# ArduinoUnoShield.net
KiCad netlist of a schematic drawn in Altium Designer
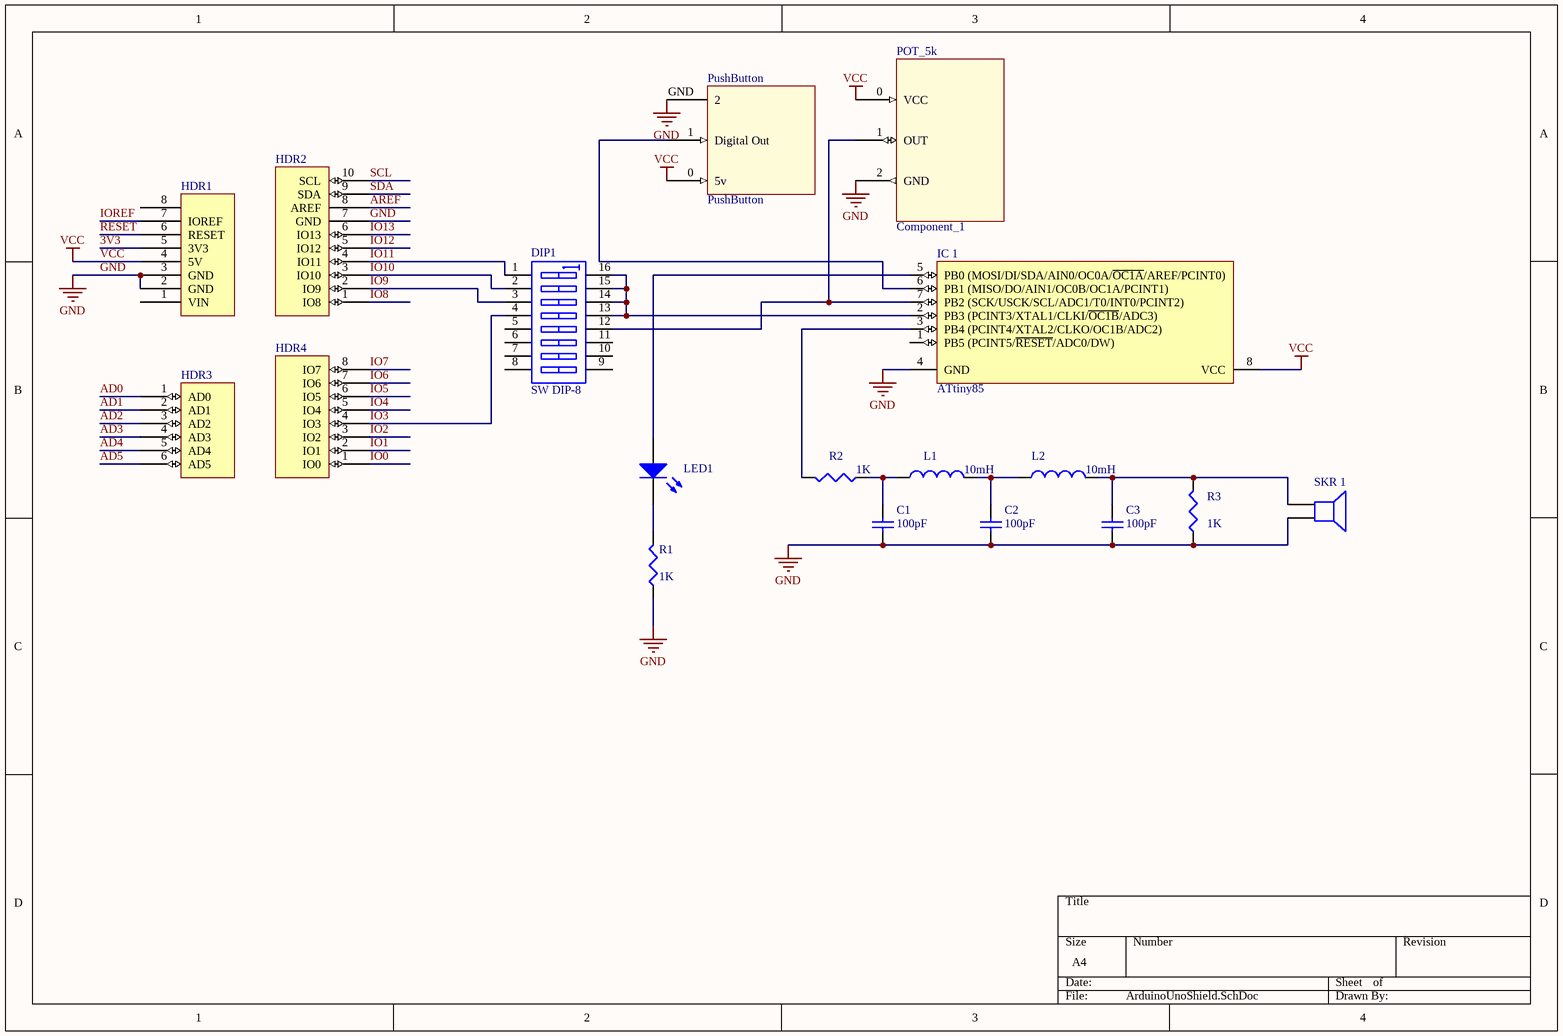
[diagram p0: ArduinoUnoShield.SchDoc]

(export (version "E")
  (design (tool "Eeschema 10.0.6"))
  (components
    (comp (ref "C1")
      (value "100pF")
      (footprint "1608[0603]")
      (description "Capacitor (Semiconductor SIM Model)")
      (fields (field (name "Comment") "Cap Semi") (field (name "PUBLISHER") "Altium Limited"))
      (libsource (lib "Miscellaneous Devices") (part "Cap Semi"))
    )
    (comp (ref "C2")
      (value "100pF")
      (footprint "1608[0603]")
      (description "Capacitor (Semiconductor SIM Model)")
      (fields (field (name "Comment") "Cap Semi") (field (name "PUBLISHER") "Altium Limited"))
      (libsource (lib "Miscellaneous Devices") (part "Cap Semi"))
    )
    (comp (ref "C3")
      (value "100pF")
      (footprint "1608[0603]")
      (description "Capacitor (Semiconductor SIM Model)")
      (fields (field (name "Comment") "Cap Semi") (field (name "PUBLISHER") "Altium Limited"))
      (libsource (lib "Miscellaneous Devices") (part "Cap Semi"))
    )
    (comp (ref "DIP1")
      (value "SW DIP-8")
      (footprint "DIP_SW_8WAY_SMD")
      (description "DIP Switch, 8 Position, SPST")
      (fields (field (name "PUBLISHER") "Altium Limited"))
      (libsource (lib "Miscellaneous Devices") (part "SW DIP-8"))
    )
    (comp (ref "HDR1")
      (value "POWER_UNO")
      (footprint "Header 8x1 8.5mm")
      (libsource (lib "Header") (part "POWER_UNO"))
    )
    (comp (ref "HDR2")
      (value "IOH")
      (footprint "Header:Header 10x1 8.5mm")
      (libsource (lib "Header") (part "IOH"))
    )
    (comp (ref "HDR3")
      (value "AD")
      (footprint "Header:Header 6x1 8.5mm")
      (libsource (lib "Header") (part "AD"))
    )
    (comp (ref "HDR4") (value "IOL") (footprint "Header 8x1 8.5mm") (libsource (lib "Header") (part "IOL")))
    (comp (ref "IC 1")
      (value "ATtiny85")
      (footprint "8P3")
      (fields (field (name "PUBLISHER") "Altium Limited"))
      (libsource (lib "Atmel Microcontroller 8-Bit tinyAVR") (part "ATtiny85-20PU"))
    )
    (comp (ref "L1")
      (value "10mH")
      (footprint "0603")
      (description "Inductor")
      (fields (field (name "PUBLISHER") "Altium Limited"))
      (libsource (lib "Miscellaneous Devices") (part "Inductor"))
    )
    (comp (ref "L2")
      (value "10mH")
      (footprint "0603")
      (description "Inductor")
      (fields (field (name "PUBLISHER") "Altium Limited"))
      (libsource (lib "Miscellaneous Devices") (part "Inductor"))
    )
    (comp (ref "LED1")
      (value "LED1")
      (footprint "LED-1")
      (description "Typical RED GaAs LED")
      (fields (field (name "PUBLISHER") "Altium Limited"))
      (libsource (lib "Miscellaneous Devices") (part "LED1"))
    )
    (comp (ref "POT_5k")
      (value "Component_1")
      (footprint "PCBComponent_1")
      (description "5k RES")
      (libsource (lib "PotLib_v_2") (part "Component_1"))
    )
    (comp (ref "PushButton")
      (value "PushButton")
      (footprint "PushButtonFrame")
      (libsource (lib "Pushbutton_V_4") (part "PushButton"))
    )
    (comp (ref "R1")
      (value "1K")
      (footprint "J1-0603")
      (description "Resistor")
      (fields (field (name "PUBLISHER") "Altium Limited"))
      (libsource (lib "Miscellaneous Devices") (part "Res3"))
    )
    (comp (ref "R2")
      (value "1K")
      (footprint "J1-0603")
      (description "Resistor")
      (fields (field (name "Comment") "Res3") (field (name "PUBLISHER") "Altium Limited"))
      (libsource (lib "Miscellaneous Devices") (part "Res3"))
    )
    (comp (ref "R3")
      (value "1K")
      (footprint "J1-0603")
      (description "Resistor")
      (fields (field (name "Comment") "Res3") (field (name "PUBLISHER") "Altium Limited"))
      (libsource (lib "Miscellaneous Devices") (part "Res3"))
    )
    (comp (ref "SKR 1")
      (value "Speaker")
      (footprint "PIN2")
      (description "Loudspeaker")
      (fields (field (name "PUBLISHER") "Altium Limited"))
      (libsource (lib "Miscellaneous Devices") (part "Speaker"))
    )
  )
  (nets
    (net (code "1") (name "/3V3") (class "Default")
      (node (ref "HDR1") (pin "5") (pinfunction "3V3_5") (pintype "power_in"))
    )
    (net (code "3") (name "/AD0") (class "Default")
      (node (ref "HDR3") (pin "1") (pinfunction "AD0_1") (pintype "bidirectional"))
    )
    (net (code "4") (name "/AD1") (class "Default")
      (node (ref "HDR3") (pin "2") (pinfunction "AD1_2") (pintype "bidirectional"))
    )
    (net (code "5") (name "/AD2") (class "Default")
      (node (ref "HDR3") (pin "3") (pinfunction "AD2_3") (pintype "bidirectional"))
    )
    (net (code "6") (name "/AD3") (class "Default")
      (node (ref "HDR3") (pin "4") (pinfunction "AD3_4") (pintype "bidirectional"))
    )
    (net (code "7") (name "/AD4") (class "Default")
      (node (ref "HDR3") (pin "5") (pinfunction "AD4_5") (pintype "bidirectional"))
    )
    (net (code "8") (name "/AD5") (class "Default")
      (node (ref "HDR3") (pin "6") (pinfunction "AD5_6") (pintype "bidirectional"))
    )
    (net (code "9") (name "/AREF") (class "Default")
      (node (ref "HDR2") (pin "8") (pinfunction "AREF_8") (pintype "passive"))
    )
    (net (code "10") (name "/IO0") (class "Default")
      (node (ref "HDR4") (pin "1") (pinfunction "IO0_1") (pintype "bidirectional"))
    )
    (net (code "11") (name "/IO1") (class "Default")
      (node (ref "HDR4") (pin "2") (pinfunction "IO1_2") (pintype "bidirectional"))
    )
    (net (code "12") (name "/IO2") (class "Default")
      (node (ref "HDR4") (pin "3") (pinfunction "IO2_3") (pintype "bidirectional"))
    )
    (net (code "13") (name "/IO3") (class "Default")
      (node (ref "DIP1") (pin "4") (pinfunction "A4_4") (pintype "passive"))
      (node (ref "HDR4") (pin "4") (pinfunction "IO3_4") (pintype "bidirectional"))
    )
    (net (code "14") (name "/IO4") (class "Default")
      (node (ref "HDR4") (pin "5") (pinfunction "IO4_5") (pintype "bidirectional"))
    )
    (net (code "15") (name "/IO5") (class "Default")
      (node (ref "HDR4") (pin "6") (pinfunction "IO5_6") (pintype "bidirectional"))
    )
    (net (code "16") (name "/IO6") (class "Default")
      (node (ref "HDR4") (pin "7") (pinfunction "IO6_7") (pintype "bidirectional"))
    )
    (net (code "17") (name "/IO7") (class "Default")
      (node (ref "HDR4") (pin "8") (pinfunction "IO7_8") (pintype "bidirectional"))
    )
    (net (code "18") (name "/IO8") (class "Default")
      (node (ref "HDR2") (pin "1") (pinfunction "IO8_1") (pintype "bidirectional"))
    )
    (net (code "19") (name "/IO9") (class "Default")
      (node (ref "DIP1") (pin "3") (pinfunction "A3_3") (pintype "passive"))
      (node (ref "HDR2") (pin "2") (pinfunction "IO9_2") (pintype "bidirectional"))
    )
    (net (code "20") (name "/IO10") (class "Default")
      (node (ref "DIP1") (pin "2") (pinfunction "A2_2") (pintype "passive"))
      (node (ref "HDR2") (pin "3") (pinfunction "IO10_3") (pintype "bidirectional"))
    )
    (net (code "21") (name "/IO11") (class "Default")
      (node (ref "DIP1") (pin "1") (pinfunction "A1_1") (pintype "passive"))
      (node (ref "HDR2") (pin "4") (pinfunction "IO11_4") (pintype "bidirectional"))
    )
    (net (code "22") (name "/IO12") (class "Default")
      (node (ref "HDR2") (pin "5") (pinfunction "IO12_5") (pintype "bidirectional"))
    )
    (net (code "23") (name "/IO13") (class "Default")
      (node (ref "HDR2") (pin "6") (pinfunction "IO13_6") (pintype "bidirectional"))
    )
    (net (code "24") (name "/IOREF") (class "Default")
      (node (ref "HDR1") (pin "7") (pinfunction "IOREF_7") (pintype "power_in"))
    )
    (net (code "25") (name "/RESET") (class "Default")
      (node (ref "HDR1") (pin "6") (pinfunction "RESET_6") (pintype "passive"))
    )
    (net (code "26") (name "/SCL") (class "Default")
      (node (ref "HDR2") (pin "10") (pinfunction "SCL_10") (pintype "bidirectional"))
    )
    (net (code "27") (name "/SDA") (class "Default")
      (node (ref "HDR2") (pin "9") (pinfunction "SDA_9") (pintype "bidirectional"))
    )
    (net (code "28") (name "GND") (class "Default")
      (node (ref "C1") (pin "1") (pinfunction "1_1") (pintype "passive"))
      (node (ref "C2") (pin "1") (pinfunction "1_1") (pintype "passive"))
      (node (ref "C3") (pin "1") (pinfunction "1_1") (pintype "passive"))
      (node (ref "HDR1") (pin "2") (pinfunction "GND_2") (pintype "power_in"))
      (node (ref "HDR1") (pin "3") (pinfunction "GND_3") (pintype "power_in"))
      (node (ref "HDR2") (pin "7") (pinfunction "GND_7") (pintype "power_in"))
      (node (ref "IC 1") (pin "4") (pinfunction "GND_4") (pintype "power_in"))
      (node (ref "POT_5k") (pin "2") (pinfunction "GND_2") (pintype "output"))
      (node (ref "PushButton") (pin "GND") (pinfunction "2_GND") (pintype "power_in"))
      (node (ref "R1") (pin "1") (pinfunction "1_1") (pintype "passive"))
      (node (ref "R3") (pin "1") (pinfunction "1_1") (pintype "passive"))
      (node (ref "SKR 1") (pin "2") (pinfunction "2_2") (pintype "passive"))
    )
    (net (code "29") (name "Net-(C1-Pad2)") (class "Default")
      (node (ref "C1") (pin "2") (pinfunction "2_2") (pintype "passive"))
      (node (ref "L1") (pin "1") (pinfunction "1_1") (pintype "passive"))
      (node (ref "R2") (pin "1") (pinfunction "1_1") (pintype "passive"))
    )
    (net (code "30") (name "Net-(C2-Pad2)") (class "Default")
      (node (ref "C2") (pin "2") (pinfunction "2_2") (pintype "passive"))
      (node (ref "L1") (pin "2") (pinfunction "2_2") (pintype "passive"))
      (node (ref "L2") (pin "1") (pinfunction "1_1") (pintype "passive"))
    )
    (net (code "31") (name "Net-(C3-Pad2)") (class "Default")
      (node (ref "C3") (pin "2") (pinfunction "2_2") (pintype "passive"))
      (node (ref "L2") (pin "2") (pinfunction "2_2") (pintype "passive"))
      (node (ref "R3") (pin "2") (pinfunction "2_2") (pintype "passive"))
      (node (ref "SKR 1") (pin "1") (pinfunction "1_1") (pintype "passive"))
    )
    (net (code "32") (name "Net-(DIP1-B1)") (class "Default")
      (node (ref "DIP1") (pin "13") (pinfunction "B4_13") (pintype "passive"))
      (node (ref "DIP1") (pin "14") (pinfunction "B3_14") (pintype "passive"))
      (node (ref "DIP1") (pin "15") (pinfunction "B2_15") (pintype "passive"))
      (node (ref "DIP1") (pin "16") (pinfunction "B1_16") (pintype "passive"))
      (node (ref "IC 1") (pin "2") (pinfunction "PB3_(PCINT3/XTAL1/CLKI/~{OC1B}/ADC3)_2") (pintype "bidirectional"))
    )
    (net (code "33") (name "Net-(DIP1-B5)") (class "Default")
      (node (ref "DIP1") (pin "12") (pinfunction "B5_12") (pintype "passive"))
      (node (ref "IC 1") (pin "7") (pinfunction "PB2_(SCK/USCK/SCL/ADC1/T0/INT0/PCINT2)_7") (pintype "bidirectional"))
      (node (ref "POT_5k") (pin "1") (pinfunction "OUT_1") (pintype "bidirectional"))
    )
    (net (code "34") (name "Net-(IC 1-PB0_(MOSI{slash}DI{slash}SDA{slash}AIN0{slash}OC0A{slash}~{OC1A}{slash}AREF{slash}PCINT0))") (class "Default")
      (node (ref "IC 1") (pin "5") (pinfunction "PB0_(MOSI/DI/SDA/AIN0/OC0A/~{OC1A}/AREF/PCINT0)_5") (pintype "bidirectional"))
      (node (ref "LED1") (pin "1") (pinfunction "A_1") (pintype "passive"))
    )
    (net (code "35") (name "Net-(IC 1-PB1_(MISO{slash}DO{slash}AIN1{slash}OC0B{slash}OC1A{slash}PCINT1))") (class "Default")
      (node (ref "IC 1") (pin "6") (pinfunction "PB1_(MISO/DO/AIN1/OC0B/OC1A/PCINT1)_6") (pintype "bidirectional"))
      (node (ref "PushButton") (pin "1") (pinfunction "Digital_Out_1") (pintype "input"))
    )
    (net (code "36") (name "Net-(IC 1-PB4_(PCINT4{slash}XTAL2{slash}CLKO{slash}OC1B{slash}ADC2))") (class "Default")
      (node (ref "IC 1") (pin "3") (pinfunction "PB4_(PCINT4/XTAL2/CLKO/OC1B/ADC2)_3") (pintype "bidirectional"))
      (node (ref "R2") (pin "2") (pinfunction "2_2") (pintype "passive"))
    )
    (net (code "37") (name "Net-(LED1-K)") (class "Default")
      (node (ref "LED1") (pin "2") (pinfunction "K_2") (pintype "passive"))
      (node (ref "R1") (pin "2") (pinfunction "2_2") (pintype "passive"))
    )
    (net (code "38") (name "VCC") (class "Default")
      (node (ref "HDR1") (pin "4") (pinfunction "5V_4") (pintype "power_in"))
      (node (ref "IC 1") (pin "8") (pinfunction "VCC_8") (pintype "power_in"))
      (node (ref "POT_5k") (pin "0") (pinfunction "VCC_0") (pintype "input"))
      (node (ref "PushButton") (pin "0") (pinfunction "5v_0") (pintype "input"))
    )
    (net (code "39") (name "unconnected-(DIP1-A5-Pad5)") (class "Default")
      (node (ref "DIP1") (pin "5") (pinfunction "A5_5") (pintype "passive"))
    )
    (net (code "40") (name "unconnected-(DIP1-A6-Pad6)") (class "Default")
      (node (ref "DIP1") (pin "6") (pinfunction "A6_6") (pintype "passive"))
    )
    (net (code "41") (name "unconnected-(DIP1-A7-Pad7)") (class "Default")
      (node (ref "DIP1") (pin "7") (pinfunction "A7_7") (pintype "passive"))
    )
    (net (code "42") (name "unconnected-(DIP1-A8-Pad8)") (class "Default")
      (node (ref "DIP1") (pin "8") (pinfunction "A8_8") (pintype "passive"))
    )
    (net (code "43") (name "unconnected-(DIP1-B6-Pad11)") (class "Default")
      (node (ref "DIP1") (pin "11") (pinfunction "B6_11") (pintype "passive"))
    )
    (net (code "44") (name "unconnected-(DIP1-B7-Pad10)") (class "Default")
      (node (ref "DIP1") (pin "10") (pinfunction "B7_10") (pintype "passive"))
    )
    (net (code "45") (name "unconnected-(DIP1-B8-Pad9)") (class "Default")
      (node (ref "DIP1") (pin "9") (pinfunction "B8_9") (pintype "passive"))
    )
    (net (code "46") (name "unconnected-(HDR1-Pad8)") (class "Default")
      (node (ref "HDR1") (pin "8") (pintype "passive"))
    )
    (net (code "47") (name "unconnected-(HDR1-VIN-Pad1)") (class "Default")
      (node (ref "HDR1") (pin "1") (pinfunction "VIN_1") (pintype "power_in"))
    )
    (net (code "48") (name "unconnected-(IC 1-PB5_(PCINT5{slash}~{RESET}{slash}ADC0{slash}DW)-Pad1)") (class "Default")
      (node (ref "IC 1") (pin "1") (pinfunction "PB5_(PCINT5/~{RESET}/ADC0/DW)_1") (pintype "bidirectional"))
    )
  )
)
